# RealTime.net
KiCad netlist of a schematic drawn in Altium Designer
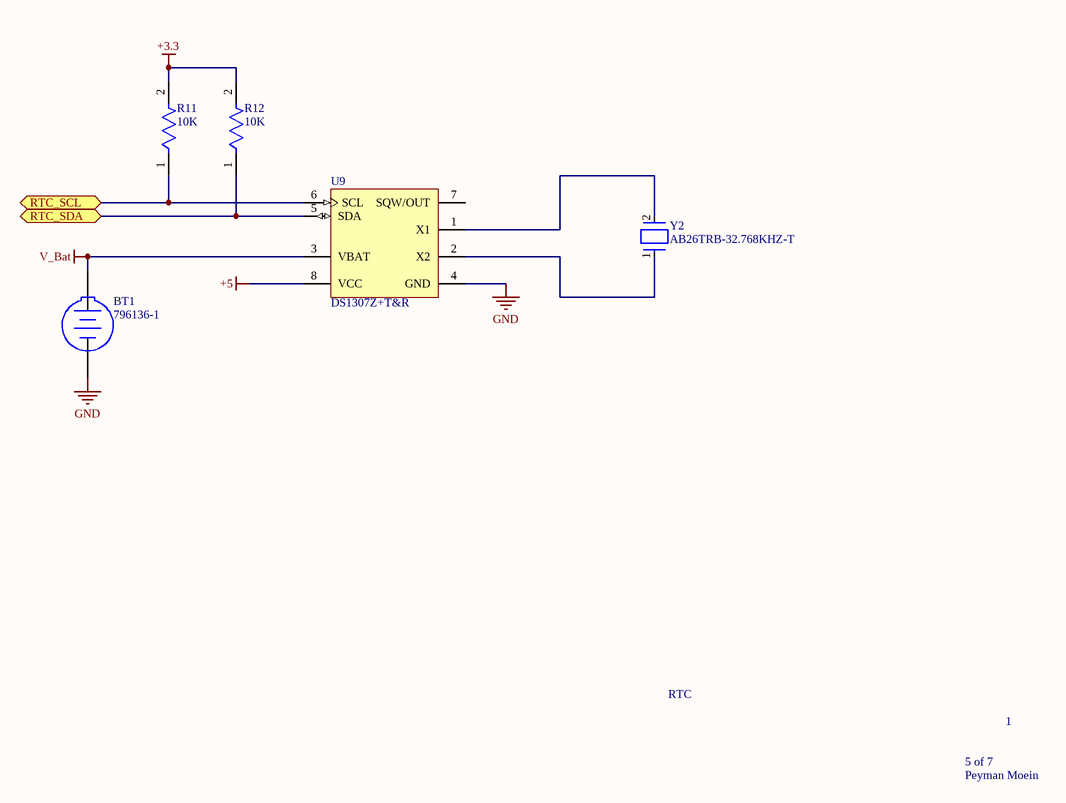
[diagram p0: RealTime.SchDoc]

(export (version "E")
  (design (tool "Eeschema 10.0.6"))
  (components
    (comp (ref "BT1")
      (value "796136-1")
      (footprint "TECO-796136-1_V")
      (description "C70377")
      (libsource (lib "Altium Content Vault") (part "BATTERY-HOLDER-COIN-2"))
    )
    (comp (ref "R11")
      (value "10K")
      (footprint "FP-CRCW0805-e3-MFG")
      (description "C478887")
      (fields (field (name "TOLERANCE") "1%"))
      (libsource (lib "Altium Content Vault") (part "1029c3af85768c4190bb7ad29bc67b5"))
    )
    (comp (ref "R12")
      (value "10K")
      (footprint "FP-CRCW0805-e3-MFG")
      (description "C478887")
      (fields (field (name "TOLERANCE") "1%"))
      (libsource (lib "Altium Content Vault") (part "1029c3af85768c4190bb7ad29bc67b5"))
    )
    (comp (ref "U9")
      (value "DS1307Z+T&R")
      (footprint "S8+2_L")
      (description "C9868")
      (libsource (lib "Altium Content Vault") (part "PR_RTC_DS1307-IL8"))
    )
    (comp (ref "Y2")
      (value "AB26TRB-32.768KHZ-T")
      (footprint "FP-AB26TRB-MFG")
      (description "C179645")
      (fields (field (name "TOLERANCE") "20ppm"))
      (libsource (lib "Altium Content Vault") (part "c23a69dc6c9e2f18f2079038eb95dd1"))
    )
  )
  (nets
    (net (code "1") (name "+3.3") (class "Default")
      (node (ref "R11") (pin "2") (pinfunction "2_2") (pintype "passive"))
      (node (ref "R12") (pin "2") (pinfunction "2_2") (pintype "passive"))
    )
    (net (code "2") (name "+5") (class "Default")
      (node (ref "U9") (pin "8") (pinfunction "VCC_8") (pintype "power_in"))
    )
    (net (code "3") (name "/RTC_SCL") (class "Default")
      (node (ref "R11") (pin "1") (pinfunction "1_1") (pintype "passive"))
      (node (ref "U9") (pin "6") (pinfunction "SCL_6") (pintype "input"))
    )
    (net (code "4") (name "/RTC_SDA") (class "Default")
      (node (ref "R12") (pin "1") (pinfunction "1_1") (pintype "passive"))
      (node (ref "U9") (pin "5") (pinfunction "SDA_5") (pintype "bidirectional"))
    )
    (net (code "5") (name "GND") (class "Default")
      (node (ref "BT1") (pin "2") (pinfunction "-_2") (pintype "passive"))
      (node (ref "U9") (pin "4") (pinfunction "GND_4") (pintype "power_in"))
    )
    (net (code "6") (name "Net-(U9-X1)") (class "Default")
      (node (ref "U9") (pin "1") (pinfunction "X1_1") (pintype "passive"))
      (node (ref "Y2") (pin "2") (pinfunction "2_2") (pintype "passive"))
    )
    (net (code "7") (name "Net-(U9-X2)") (class "Default")
      (node (ref "U9") (pin "2") (pinfunction "X2_2") (pintype "passive"))
      (node (ref "Y2") (pin "1") (pinfunction "1_1") (pintype "passive"))
    )
    (net (code "8") (name "V_Bat") (class "Default")
      (node (ref "BT1") (pin "1") (pinfunction "+_1") (pintype "passive"))
      (node (ref "U9") (pin "3") (pinfunction "VBAT_3") (pintype "power_in"))
    )
    (net (code "9") (name "unconnected-(U9-SQW{slash}OUT-Pad7)") (class "Default")
      (node (ref "U9") (pin "7") (pinfunction "SQW/OUT_7") (pintype "open_collector"))
    )
  )
)
